# Probe.net
KiCad netlist of a schematic drawn in Altium Designer
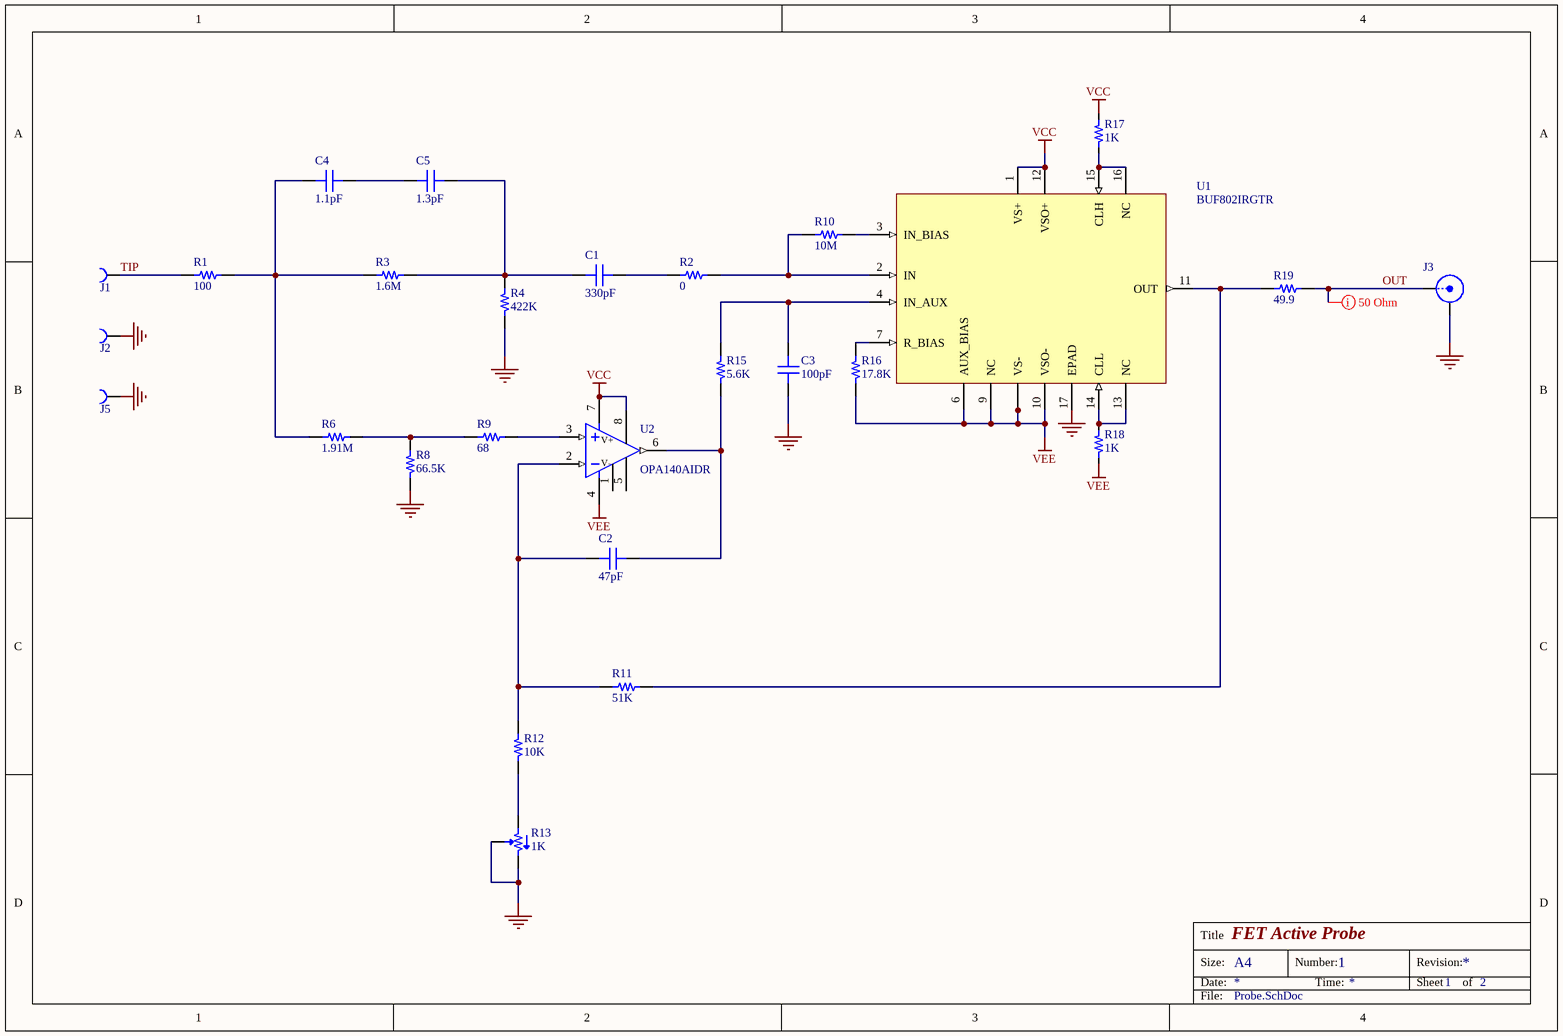
[diagram p0: Probe.SchDoc]

(export (version "E")
  (design (tool "Eeschema 10.0.6"))
  (components
    (comp (ref "C1")
      (value "330pF")
      (footprint "CAP 0402/1005")
      (description "CAP CER 330PF 50V NP0 0402")
      (fields (field (name "MANUFACTURER") "Murata") (field (name "TOLERANCE") "5%"))
      (libsource (lib "Mengsklib") (part "Capacitor"))
    )
    (comp (ref "C2")
      (value "47pF")
      (footprint "CAP 0402/1005")
      (description "CAP CER 47PF 50V NP0 0402")
      (fields (field (name "MANUFACTURER") "Murata") (field (name "TOLERANCE") "1%"))
      (libsource (lib "Mengsklib") (part "Capacitor"))
    )
    (comp (ref "C3")
      (value "100pF")
      (footprint "CAP 0402/1005")
      (description "CAP CER 100PF 50V NP0 0402")
      (fields (field (name "MANUFACTURER") "Murata") (field (name "TOLERANCE") "1%"))
      (libsource (lib "Mengsklib") (part "Capacitor"))
    )
    (comp (ref "C4")
      (value "1.1pF")
      (footprint "CAP 0402/1005 RF")
      (description "CAP CER 1.1PF +-0.05PF 50V NP0 0201")
      (fields (field (name "PART NUMBER") "GJM1555C1H1R1WB01D") (field (name "MANUFACTURER") "Murata"))
      (libsource (lib "Mengsklib") (part "Capacitor"))
    )
    (comp (ref "C5")
      (value "1.3pF")
      (footprint "CAP 0402/1005 RF")
      (description "CAP CER 1.3PF +-0.05PF 50V NP0 0201")
      (fields (field (name "PART NUMBER") "GJM1555C1H1R3WB01D") (field (name "TOLERANCE") "0.05pF"))
      (libsource (lib "Mengsklib") (part "Capacitor"))
    )
    (comp (ref "J1")
      (value "0339-0-15-01-15-27-10-0")
      (footprint "MILL-MAX 0339")
      (description "CONN PIN RCPT")
      (fields (field (name "MANUFACTURER") "Mill-Max"))
      (libsource (lib "Connectors") (part "0339-0-15-01-15-27-10-0"))
    )
    (comp (ref "J2")
      (value "0339-0-15-01-15-27-10-0")
      (footprint "MILL-MAX 0339")
      (description "CONN PIN RCPT")
      (fields (field (name "MANUFACTURER") "Mill-Max"))
      (libsource (lib "Connectors") (part "0339-0-15-01-15-27-10-0"))
    )
    (comp (ref "J3")
      (value "CONN SMA JACK EDGE MNT")
      (footprint "60312202114513")
      (description "WR-SMA Connector, PCB End Launch Jack, 6.35SQ Flange Flat Tab 1.6mm, DC~18GHz, 50Ohm")
      (fields (field (name "PART NUMBER") "60312202114513") (field (name "MANUFACTURER") "Wurth"))
      (libsource (lib "Mengsklib") (part "CONN RF Coaxial"))
    )
    (comp (ref "J5")
      (value "0339-0-15-01-15-27-10-0")
      (footprint "MILL-MAX 0339")
      (description "CONN PIN RCPT")
      (fields (field (name "MANUFACTURER") "Mill-Max"))
      (libsource (lib "Connectors") (part "0339-0-15-01-15-27-10-0"))
    )
    (comp (ref "R1")
      (value "100")
      (footprint "RES 0402/1005")
      (description "RES SMD 100 OHM 1% 1/16W 0402")
      (fields (field (name "PART NUMBER") "RC0402FR-07100RL") (field (name "MANUFACTURER") "Yageo"))
      (libsource (lib "Mengsklib") (part "Resistor"))
    )
    (comp (ref "R2")
      (value "0")
      (footprint "RES 0402/1005")
      (description "RES SMD 0 OHM 5% 1/16W 0402")
      (fields (field (name "PART NUMBER") "RC0402JR-070RL") (field (name "MANUFACTURER") "Yageo"))
      (libsource (lib "Mengsklib") (part "Resistor"))
    )
    (comp (ref "R3")
      (value "1.6M")
      (footprint "RES 0402/1005")
      (description "RES SMD 1.6M OHM 1% 1/16W 0402")
      (fields (field (name "PART NUMBER") "RC0402FR-071M6L") (field (name "MANUFACTURER") "Yageo"))
      (libsource (lib "Mengsklib") (part "Resistor"))
    )
    (comp (ref "R4")
      (value "422K")
      (footprint "RES 0402/1005")
      (description "RES SMD 422K OHM 1% 1/16W 0402")
      (fields (field (name "PART NUMBER") "RC0402FR-07422KL") (field (name "MANUFACTURER") "Yageo"))
      (libsource (lib "Mengsklib") (part "Resistor"))
    )
    (comp (ref "R6")
      (value "1.91M")
      (footprint "RES 0402/1005")
      (description "RES SMD 1.91M OHM 1% 1/16W 0402")
      (fields (field (name "PART NUMBER") "RC0402FR-071M91L") (field (name "MANUFACTURER") "Yageo"))
      (libsource (lib "Mengsklib") (part "Resistor"))
    )
    (comp (ref "R8")
      (value "66.5K")
      (footprint "RES 0402/1005")
      (description "RES SMD 66.5K OHM 1% 1/16W 0402")
      (fields (field (name "PART NUMBER") "RC0402FR-0766K5L") (field (name "MANUFACTURER") "Yageo"))
      (libsource (lib "Mengsklib") (part "Resistor"))
    )
    (comp (ref "R9")
      (value "68")
      (footprint "RES 0402/1005")
      (description "RES SMD 68 OHM 1% 1/16W 0402")
      (fields (field (name "PART NUMBER") "RC0402FR-0768RL") (field (name "MANUFACTURER") "Yageo"))
      (libsource (lib "Mengsklib") (part "Resistor"))
    )
    (comp (ref "R10")
      (value "10M")
      (footprint "RES 0402/1005")
      (description "RES SMD 10M OHM 1% 1/16W 0402")
      (fields (field (name "PART NUMBER") "RC0402FR-0710ML") (field (name "MANUFACTURER") "Yageo"))
      (libsource (lib "Mengsklib") (part "Resistor"))
    )
    (comp (ref "R11")
      (value "51K")
      (footprint "RES 0402/1005")
      (description "RES SMD 51K OHM 1% 1/16W 0402")
      (fields (field (name "PART NUMBER") "RC0402FR-0751KL") (field (name "MANUFACTURER") "Yageo"))
      (libsource (lib "Mengsklib") (part "Resistor"))
    )
    (comp (ref "R12")
      (value "10K")
      (footprint "RES 0402/1005")
      (description "RES SMD 10K OHM 1% 1/16W 0402")
      (fields (field (name "PART NUMBER") "RC0402FR-0710KL") (field (name "MANUFACTURER") "Yageo"))
      (libsource (lib "Mengsklib") (part "Resistor"))
    )
    (comp (ref "R13")
      (value "1K")
      (footprint "BOURNS 3224W")
      (description "TRIMMER 1K OHM 0.25W J LEAD TOP")
      (fields (field (name "MANUFACTURER") "Bourns") (field (name "TOLERANCE") "10%"))
      (libsource (lib "Mengsklib") (part "Potentiometer"))
    )
    (comp (ref "R15")
      (value "5.6K")
      (footprint "RES 0402/1005")
      (description "RES SMD 5.6K OHM 1% 1/16W 0402")
      (fields (field (name "PART NUMBER") "RC0402FR-075K6L") (field (name "MANUFACTURER") "Yageo"))
      (libsource (lib "Mengsklib") (part "Resistor"))
    )
    (comp (ref "R16")
      (value "17.8K")
      (footprint "RES 0402/1005")
      (description "RES SMD 17.8K OHM 1% 1/16W 0402")
      (fields (field (name "PART NUMBER") "RC0402FR-0717K8L") (field (name "MANUFACTURER") "Yageo"))
      (libsource (lib "Mengsklib") (part "Resistor"))
    )
    (comp (ref "R17")
      (value "1K")
      (footprint "RES 0402/1005")
      (description "RES SMD 1K OHM 1% 1/16W 0402")
      (fields (field (name "PART NUMBER") "RC0402FR-071KL") (field (name "MANUFACTURER") "Yageo"))
      (libsource (lib "") (part "Resistor_1"))
    )
    (comp (ref "R18")
      (value "1K")
      (footprint "RES 0402/1005")
      (description "RES SMD 1K OHM 1% 1/16W 0402")
      (fields (field (name "PART NUMBER") "RC0402FR-071KL") (field (name "MANUFACTURER") "Yageo"))
      (libsource (lib "") (part "Resistor_1"))
    )
    (comp (ref "R19")
      (value "49.9")
      (footprint "RES 0402/1005")
      (description "RES SMD 49.9 OHM 1% 1/16W 0402")
      (fields (field (name "PART NUMBER") "RC0402FR-0749R9L") (field (name "MANUFACTURER") "Yageo"))
      (libsource (lib "Mengsklib") (part "Resistor"))
    )
    (comp (ref "U1")
      (value "BUF802IRGTR")
      (footprint "QFN50P305X305X100_HS-17N")
      (description "IC AMP WIDE BANDWIDTH 16VQFN")
      (fields (field (name "MANUFACTURER") "TI"))
      (libsource (lib "Mengsklib") (part "BUF802IRGTR"))
    )
    (comp (ref "U2")
      (value "OPA140AIDR")
      (footprint "TI SOIC-8 D")
      (description "IC OPAMP JFET 1CIRC 8SOIC")
      (fields (field (name "MANUFACTURER") "TI"))
      (libsource (lib "Mengsklib") (part "OPAMP_1CH_8P"))
    )
  )
  (nets
    (net (code "1") (name "/OUT") (class "Default")
      (node (ref "J3") (pin "1") (pinfunction "X_1") (pintype "passive"))
      (node (ref "R19") (pin "2") (pinfunction "2_2") (pintype "passive"))
    )
    (net (code "2") (name "/TIP") (class "Default")
      (node (ref "J1") (pin "1") (pinfunction "1_1") (pintype "passive"))
      (node (ref "R1") (pin "1") (pinfunction "1_1") (pintype "passive"))
    )
    (net (code "3") (name "GND") (class "Default")
      (node (ref "C3") (pin "2") (pinfunction "2_2") (pintype "passive"))
      (node (ref "J2") (pin "1") (pinfunction "1_1") (pintype "passive"))
      (node (ref "J3") (pin "2") (pinfunction "Y_2") (pintype "passive"))
      (node (ref "J5") (pin "1") (pinfunction "1_1") (pintype "passive"))
      (node (ref "R13") (pin "2") (pinfunction "2_2") (pintype "passive"))
      (node (ref "R13") (pin "3") (pinfunction "3_3") (pintype "passive"))
      (node (ref "R4") (pin "2") (pinfunction "2_2") (pintype "passive"))
      (node (ref "R8") (pin "2") (pinfunction "2_2") (pintype "passive"))
      (node (ref "U1") (pin "17") (pinfunction "EPAD_17") (pintype "passive"))
    )
    (net (code "4") (name "Net-(C1-Pad1)") (class "Default")
      (node (ref "C1") (pin "1") (pinfunction "1_1") (pintype "passive"))
      (node (ref "C5") (pin "2") (pinfunction "2_2") (pintype "passive"))
      (node (ref "R3") (pin "2") (pinfunction "2_2") (pintype "passive"))
      (node (ref "R4") (pin "1") (pinfunction "1_1") (pintype "passive"))
    )
    (net (code "5") (name "Net-(C1-Pad2)") (class "Default")
      (node (ref "C1") (pin "2") (pinfunction "2_2") (pintype "passive"))
      (node (ref "R2") (pin "1") (pinfunction "1_1") (pintype "passive"))
    )
    (net (code "6") (name "Net-(C4-Pad1)") (class "Default")
      (node (ref "C4") (pin "1") (pinfunction "1_1") (pintype "passive"))
      (node (ref "R1") (pin "2") (pinfunction "2_2") (pintype "passive"))
      (node (ref "R3") (pin "1") (pinfunction "1_1") (pintype "passive"))
      (node (ref "R6") (pin "1") (pinfunction "1_1") (pintype "passive"))
    )
    (net (code "7") (name "Net-(C4-Pad2)") (class "Default")
      (node (ref "C4") (pin "2") (pinfunction "2_2") (pintype "passive"))
      (node (ref "C5") (pin "1") (pinfunction "1_1") (pintype "passive"))
    )
    (net (code "8") (name "Net-(R6-Pad2)") (class "Default")
      (node (ref "R6") (pin "2") (pinfunction "2_2") (pintype "passive"))
      (node (ref "R8") (pin "1") (pinfunction "1_1") (pintype "passive"))
      (node (ref "R9") (pin "1") (pinfunction "1_1") (pintype "passive"))
    )
    (net (code "9") (name "Net-(R12-Pad2)") (class "Default")
      (node (ref "R12") (pin "2") (pinfunction "2_2") (pintype "passive"))
      (node (ref "R13") (pin "1") (pinfunction "1_1") (pintype "passive"))
    )
    (net (code "10") (name "Net-(U1-CLH)") (class "Default")
      (node (ref "R17") (pin "1") (pinfunction "1_1") (pintype "passive"))
      (node (ref "U1") (pin "15") (pinfunction "CLH_15") (pintype "input"))
      (node (ref "U1") (pin "16") (pinfunction "NC_16") (pintype "passive"))
    )
    (net (code "11") (name "Net-(U1-CLL)") (class "Default")
      (node (ref "R18") (pin "1") (pinfunction "1_1") (pintype "passive"))
      (node (ref "U1") (pin "13") (pinfunction "NC_13") (pintype "passive"))
      (node (ref "U1") (pin "14") (pinfunction "CLL_14") (pintype "input"))
    )
    (net (code "12") (name "Net-(U1-IN)") (class "Default")
      (node (ref "R10") (pin "1") (pinfunction "1_1") (pintype "passive"))
      (node (ref "R2") (pin "2") (pinfunction "2_2") (pintype "passive"))
      (node (ref "U1") (pin "2") (pinfunction "IN_2") (pintype "input"))
    )
    (net (code "13") (name "Net-(U1-IN_AUX)") (class "Default")
      (node (ref "C3") (pin "1") (pinfunction "1_1") (pintype "passive"))
      (node (ref "R15") (pin "1") (pinfunction "1_1") (pintype "passive"))
      (node (ref "U1") (pin "4") (pinfunction "IN_AUX_4") (pintype "input"))
    )
    (net (code "14") (name "Net-(U1-IN_BIAS)") (class "Default")
      (node (ref "R10") (pin "2") (pinfunction "2_2") (pintype "passive"))
      (node (ref "U1") (pin "3") (pinfunction "IN_BIAS_3") (pintype "input"))
    )
    (net (code "15") (name "Net-(U1-OUT)") (class "Default")
      (node (ref "R11") (pin "2") (pinfunction "2_2") (pintype "passive"))
      (node (ref "R19") (pin "1") (pinfunction "1_1") (pintype "passive"))
      (node (ref "U1") (pin "11") (pinfunction "OUT_11") (pintype "output"))
    )
    (net (code "16") (name "Net-(U1-R_BIAS)") (class "Default")
      (node (ref "R16") (pin "1") (pinfunction "1_1") (pintype "passive"))
      (node (ref "U1") (pin "7") (pinfunction "R_BIAS_7") (pintype "input"))
    )
    (net (code "17") (name "Net-(U2-+IN)") (class "Default")
      (node (ref "R9") (pin "2") (pinfunction "2_2") (pintype "passive"))
      (node (ref "U2") (pin "3") (pinfunction "+IN_3") (pintype "input"))
    )
    (net (code "18") (name "Net-(U2--IN)") (class "Default")
      (node (ref "C2") (pin "1") (pinfunction "1_1") (pintype "passive"))
      (node (ref "R11") (pin "1") (pinfunction "1_1") (pintype "passive"))
      (node (ref "R12") (pin "1") (pinfunction "1_1") (pintype "passive"))
      (node (ref "U2") (pin "2") (pinfunction "-IN_2") (pintype "input"))
    )
    (net (code "19") (name "Net-(U2-OUT)") (class "Default")
      (node (ref "C2") (pin "2") (pinfunction "2_2") (pintype "passive"))
      (node (ref "R15") (pin "2") (pinfunction "2_2") (pintype "passive"))
      (node (ref "U2") (pin "6") (pinfunction "OUT_6") (pintype "output"))
    )
    (net (code "20") (name "VCC") (class "Default")
      (node (ref "R17") (pin "2") (pinfunction "2_2") (pintype "passive"))
      (node (ref "U1") (pin "1") (pinfunction "VS+_1") (pintype "power_in"))
      (node (ref "U1") (pin "12") (pinfunction "VSO+_12") (pintype "power_in"))
      (node (ref "U2") (pin "7") (pinfunction "V+_7") (pintype "power_in"))
      (node (ref "U2") (pin "8") (pinfunction "8_8") (pintype "passive"))
    )
    (net (code "21") (name "VEE") (class "Default")
      (node (ref "R16") (pin "2") (pinfunction "2_2") (pintype "passive"))
      (node (ref "R18") (pin "2") (pinfunction "2_2") (pintype "passive"))
      (node (ref "U1") (pin "10") (pinfunction "VSO-_10") (pintype "power_in"))
      (node (ref "U1") (pin "5") (pinfunction "VS-_5") (pintype "power_in"))
      (node (ref "U1") (pin "6") (pinfunction "AUX_BIAS_6") (pintype "power_in"))
      (node (ref "U1") (pin "8") (pinfunction "VS-_8") (pintype "power_in"))
      (node (ref "U1") (pin "9") (pinfunction "NC_9") (pintype "passive"))
      (node (ref "U2") (pin "4") (pinfunction "V-_4") (pintype "power_in"))
    )
    (net (code "22") (name "unconnected-(U2-10-Pad5)") (class "Default")
      (node (ref "U2") (pin "5") (pinfunction "10_5") (pintype "passive"))
    )
    (net (code "23") (name "unconnected-(U2-Pad1)") (class "Default")
      (node (ref "U2") (pin "1") (pinfunction "1_1") (pintype "passive"))
    )
  )
)
